# heatingHeaderEQ3.net
KiCad netlist of a schematic drawn in EAGLE
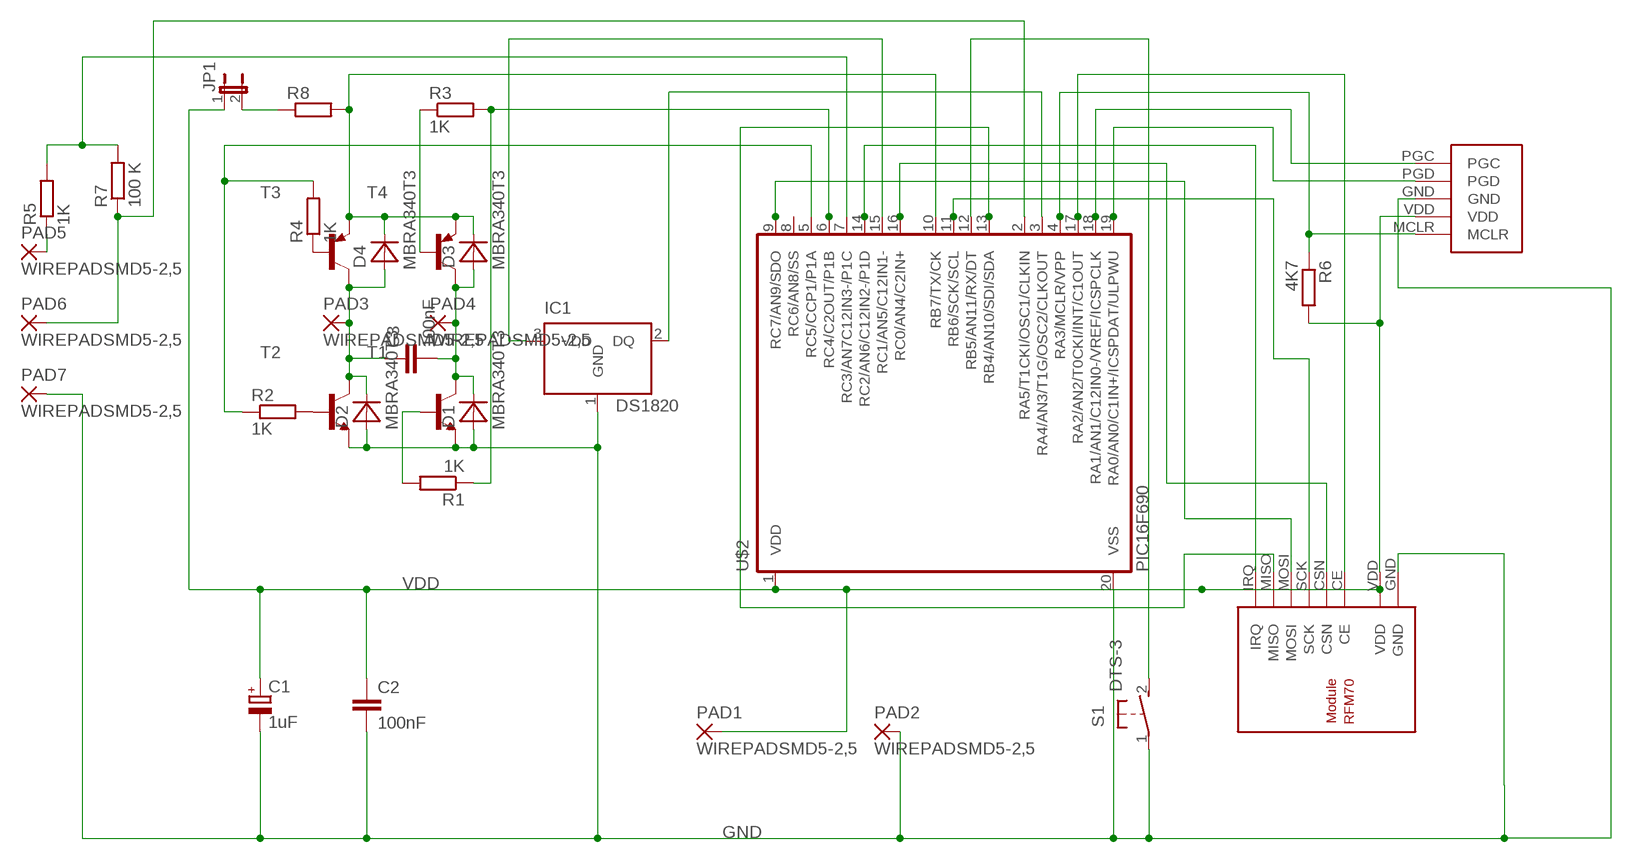
[diagram p0: schematic, sheet 1]

(export (version "E")
  (design (tool "Eeschema 10.0.6"))
  (components
    (comp (ref "C1")
      (value "1uF")
      (footprint "eagle-import:SMC_A")
      (libsource (lib "eagle-import") (part "CPOL-EUSMCA"))
    )
    (comp (ref "C2")
      (value "100nF")
      (footprint "eagle-import:C2012")
      (libsource (lib "eagle-import") (part "C-EUC2012"))
    )
    (comp (ref "C3")
      (value "100nF")
      (footprint "eagle-import:C2012")
      (libsource (lib "eagle-import") (part "C-EUC2012"))
    )
    (comp (ref "D1")
      (value "MBRA340T3")
      (footprint "eagle-import:SMA")
      (libsource (lib "eagle-import") (part "MBRA340T3"))
    )
    (comp (ref "D2")
      (value "MBRA340T3")
      (footprint "eagle-import:SMA")
      (libsource (lib "eagle-import") (part "MBRA340T3"))
    )
    (comp (ref "D3")
      (value "MBRA340T3")
      (footprint "eagle-import:SMA")
      (libsource (lib "eagle-import") (part "MBRA340T3"))
    )
    (comp (ref "D4")
      (value "MBRA340T3")
      (footprint "eagle-import:SMA")
      (libsource (lib "eagle-import") (part "MBRA340T3"))
    )
    (comp (ref "IC1")
      (value "DS1820")
      (footprint "eagle-import:TO-92")
      (libsource (lib "eagle-import") (part "DS1820"))
    )
    (comp (ref "JP1")
      (value "JP1E")
      (footprint "eagle-import:JP1")
      (libsource (lib "eagle-import") (part "JP1E"))
    )
    (comp (ref "PAD1")
      (value "WIREPADSMD5-2,5")
      (footprint "eagle-import:5-2,5")
      (libsource (lib "eagle-import") (part "WIREPADSMD5-2,5"))
    )
    (comp (ref "PAD2")
      (value "WIREPADSMD5-2,5")
      (footprint "eagle-import:5-2,5")
      (libsource (lib "eagle-import") (part "WIREPADSMD5-2,5"))
    )
    (comp (ref "PAD3")
      (value "WIREPADSMD5-2,5")
      (footprint "eagle-import:5-2,5")
      (libsource (lib "eagle-import") (part "WIREPADSMD5-2,5"))
    )
    (comp (ref "PAD4")
      (value "WIREPADSMD5-2,5")
      (footprint "eagle-import:5-2,5")
      (libsource (lib "eagle-import") (part "WIREPADSMD5-2,5"))
    )
    (comp (ref "PAD5")
      (value "WIREPADSMD5-2,5")
      (footprint "eagle-import:5-2,5")
      (libsource (lib "eagle-import") (part "WIREPADSMD5-2,5"))
    )
    (comp (ref "PAD6")
      (value "WIREPADSMD5-2,5")
      (footprint "eagle-import:5-2,5")
      (libsource (lib "eagle-import") (part "WIREPADSMD5-2,5"))
    )
    (comp (ref "PAD7")
      (value "WIREPADSMD5-2,5")
      (footprint "eagle-import:5-2,5")
      (libsource (lib "eagle-import") (part "WIREPADSMD5-2,5"))
    )
    (comp (ref "R1")
      (value "1K")
      (footprint "eagle-import:R1206")
      (libsource (lib "eagle-import") (part "R-EU_R1206"))
    )
    (comp (ref "R2")
      (value "1K")
      (footprint "eagle-import:R1206")
      (libsource (lib "eagle-import") (part "R-EU_R1206"))
    )
    (comp (ref "R3")
      (value "1K")
      (footprint "eagle-import:R1206")
      (libsource (lib "eagle-import") (part "R-EU_R1206"))
    )
    (comp (ref "R4")
      (value "1K")
      (footprint "eagle-import:R1206")
      (libsource (lib "eagle-import") (part "R-EU_R1206"))
    )
    (comp (ref "R5")
      (value "1K")
      (footprint "eagle-import:R1206")
      (libsource (lib "eagle-import") (part "R-EU_R1206"))
    )
    (comp (ref "R6")
      (value "4K7")
      (footprint "eagle-import:R1206W")
      (libsource (lib "eagle-import") (part "R-EU_R1206W"))
    )
    (comp (ref "R7")
      (value "100 K")
      (footprint "eagle-import:R1206")
      (libsource (lib "eagle-import") (part "R-EU_R1206"))
    )
    (comp (ref "R8")
      (value "R-EU_R2512W")
      (footprint "eagle-import:R2512W")
      (libsource (lib "eagle-import") (part "R-EU_R2512W"))
    )
    (comp (ref "S1")
      (value "DTS-3")
      (footprint "eagle-import:DTS-3")
      (libsource (lib "eagle-import") (part "DTS-3"))
    )
    (comp (ref "T1")
      (value "BC817-40-NPN-SOT23-BEC")
      (footprint "eagle-import:SOT23-BEC")
      (libsource (lib "eagle-import") (part "-NPN-SOT23-BECBC817-40"))
    )
    (comp (ref "T2")
      (value "BC817-40-NPN-SOT23-BEC")
      (footprint "eagle-import:SOT23-BEC")
      (libsource (lib "eagle-import") (part "-NPN-SOT23-BECBC817-40"))
    )
    (comp (ref "T3")
      (value "BC807-16-PNP-SOT23-BEC")
      (footprint "eagle-import:SOT23-BEC")
      (libsource (lib "eagle-import") (part "-PNP-SOT23-BECBC807-16"))
    )
    (comp (ref "T4")
      (value "BC807-16-PNP-SOT23-BEC")
      (footprint "eagle-import:SOT23-BEC")
      (libsource (lib "eagle-import") (part "-PNP-SOT23-BECBC807-16"))
    )
    (comp (ref "U$1")
      (value "RFM70")
      (footprint "eagle-import:RFM70")
      (libsource (lib "eagle-import") (part "RFM70"))
    )
    (comp (ref "U$2")
      (value "PIC16F690")
      (footprint "eagle-import:SSOP20")
      (libsource (lib "eagle-import") (part "PIC16F690"))
    )
    (comp (ref "U$3")
      (value "PROGRAMMINGHEADERDIP")
      (footprint "eagle-import:PROGHEADER")
      (libsource (lib "eagle-import") (part "PROGRAMMINGHEADERDIP"))
    )
  )
  (nets
    (net (code "1") (name "/GND") (class "Default")
      (node (ref "C1") (pin "-") (pinfunction "-_-") (pintype "passive"))
      (node (ref "C2") (pin "2") (pinfunction "2_2") (pintype "passive"))
      (node (ref "D1") (pin "A") (pinfunction "A_A") (pintype "passive"))
      (node (ref "D2") (pin "A") (pinfunction "A_A") (pintype "passive"))
      (node (ref "IC1") (pin "1") (pinfunction "GND_1") (pintype "power_in"))
      (node (ref "PAD2") (pin "1") (pinfunction "P_1") (pintype "passive"))
      (node (ref "PAD7") (pin "1") (pinfunction "P_1") (pintype "passive"))
      (node (ref "S1") (pin "1") (pinfunction "1_1") (pintype "passive"))
      (node (ref "T1") (pin "E") (pinfunction "E_E") (pintype "passive"))
      (node (ref "T2") (pin "E") (pinfunction "E_E") (pintype "passive"))
      (node (ref "U$1") (pin "GND") (pinfunction "GND_GND") (pintype "power_in"))
      (node (ref "U$2") (pin "20") (pinfunction "VSS_20") (pintype "power_in"))
      (node (ref "U$3") (pin "GND") (pinfunction "GND_GND") (pintype "power_in"))
    )
    (net (code "2") (name "/VDD") (class "Default")
      (node (ref "C1") (pin "+") (pinfunction "+_+") (pintype "passive"))
      (node (ref "C2") (pin "1") (pinfunction "1_1") (pintype "passive"))
      (node (ref "JP1") (pin "1") (pinfunction "1_1") (pintype "passive"))
      (node (ref "PAD1") (pin "1") (pinfunction "P_1") (pintype "passive"))
      (node (ref "R6") (pin "2") (pinfunction "2_2") (pintype "passive"))
      (node (ref "U$1") (pin "VDD") (pinfunction "VDD_VDD") (pintype "power_in"))
      (node (ref "U$2") (pin "1") (pinfunction "VDD_1") (pintype "power_in"))
      (node (ref "U$3") (pin "VDD") (pinfunction "VDD_VDD") (pintype "power_in"))
    )
    (net (code "3") (name "Net-(IC1-DQ)") (class "Default")
      (node (ref "IC1") (pin "2") (pinfunction "DQ_2") (pintype "output"))
      (node (ref "U$2") (pin "3") (pinfunction "RA4/AN3/T1G/OSC2/CLKOUT_3") (pintype "bidirectional"))
    )
    (net (code "4") (name "Net-(IC1-VDD)") (class "Default")
      (node (ref "IC1") (pin "3") (pinfunction "VDD_3") (pintype "input"))
      (node (ref "U$2") (pin "15") (pinfunction "RC1/AN5/C12IN1-_15") (pintype "bidirectional"))
    )
    (net (code "5") (name "Net-(JP1-Pad2)") (class "Default")
      (node (ref "JP1") (pin "2") (pinfunction "2_2") (pintype "passive"))
      (node (ref "R8") (pin "1") (pinfunction "1_1") (pintype "passive"))
    )
    (net (code "6") (name "Net-(PAD3-P)") (class "Default")
      (node (ref "C3") (pin "1") (pinfunction "1_1") (pintype "passive"))
      (node (ref "D2") (pin "C") (pinfunction "C_C") (pintype "passive"))
      (node (ref "D4") (pin "A") (pinfunction "A_A") (pintype "passive"))
      (node (ref "PAD3") (pin "1") (pinfunction "P_1") (pintype "passive"))
      (node (ref "T2") (pin "C") (pinfunction "C_C") (pintype "passive"))
      (node (ref "T3") (pin "C") (pinfunction "C_C") (pintype "passive"))
    )
    (net (code "7") (name "Net-(PAD4-P)") (class "Default")
      (node (ref "C3") (pin "2") (pinfunction "2_2") (pintype "passive"))
      (node (ref "D1") (pin "C") (pinfunction "C_C") (pintype "passive"))
      (node (ref "D3") (pin "A") (pinfunction "A_A") (pintype "passive"))
      (node (ref "PAD4") (pin "1") (pinfunction "P_1") (pintype "passive"))
      (node (ref "T1") (pin "C") (pinfunction "C_C") (pintype "passive"))
      (node (ref "T4") (pin "C") (pinfunction "C_C") (pintype "passive"))
    )
    (net (code "8") (name "Net-(PAD5-P)") (class "Default")
      (node (ref "PAD5") (pin "1") (pinfunction "P_1") (pintype "passive"))
      (node (ref "R5") (pin "1") (pinfunction "1_1") (pintype "passive"))
    )
    (net (code "9") (name "Net-(PAD6-P)") (class "Default")
      (node (ref "PAD6") (pin "1") (pinfunction "P_1") (pintype "passive"))
      (node (ref "R7") (pin "1") (pinfunction "1_1") (pintype "passive"))
      (node (ref "U$2") (pin "2") (pinfunction "RA5/T1CKI/OSC1/CLKIN_2") (pintype "bidirectional"))
    )
    (net (code "10") (name "Net-(R1-Pad2)") (class "Default")
      (node (ref "R1") (pin "2") (pinfunction "2_2") (pintype "passive"))
      (node (ref "T1") (pin "B") (pinfunction "B_B") (pintype "passive"))
    )
    (net (code "11") (name "Net-(R2-Pad2)") (class "Default")
      (node (ref "R2") (pin "2") (pinfunction "2_2") (pintype "passive"))
      (node (ref "T2") (pin "B") (pinfunction "B_B") (pintype "passive"))
    )
    (net (code "12") (name "Net-(R3-Pad1)") (class "Default")
      (node (ref "R3") (pin "1") (pinfunction "1_1") (pintype "passive"))
      (node (ref "T4") (pin "B") (pinfunction "B_B") (pintype "passive"))
    )
    (net (code "13") (name "Net-(R4-Pad1)") (class "Default")
      (node (ref "R4") (pin "1") (pinfunction "1_1") (pintype "passive"))
      (node (ref "T3") (pin "B") (pinfunction "B_B") (pintype "passive"))
    )
    (net (code "14") (name "Net-(U$2-RA0{slash}AN0{slash}C1IN+{slash}ICSPDAT{slash}ULPWU)") (class "Default")
      (node (ref "U$2") (pin "19") (pinfunction "RA0/AN0/C1IN+/ICSPDAT/ULPWU_19") (pintype "bidirectional"))
      (node (ref "U$3") (pin "PGD") (pinfunction "PGD_PGD") (pintype "bidirectional"))
    )
    (net (code "15") (name "Net-(U$2-RA1{slash}AN1{slash}C12IN0-{slash}VREF{slash}ICSPCLK)") (class "Default")
      (node (ref "U$2") (pin "18") (pinfunction "RA1/AN1/C12IN0-/VREF/ICSPCLK_18") (pintype "bidirectional"))
      (node (ref "U$3") (pin "PGC") (pinfunction "PGC_PGC") (pintype "bidirectional"))
    )
    (net (code "16") (name "Net-(U$2-RA2{slash}AN2{slash}T0CKI{slash}INT{slash}C1OUT)") (class "Default")
      (node (ref "U$1") (pin "CE") (pinfunction "CE_CE") (pintype "bidirectional"))
      (node (ref "U$2") (pin "17") (pinfunction "RA2/AN2/T0CKI/INT/C1OUT_17") (pintype "bidirectional"))
    )
    (net (code "17") (name "Net-(U$2-RA3{slash}MCLR{slash}VPP)") (class "Default")
      (node (ref "R6") (pin "1") (pinfunction "1_1") (pintype "passive"))
      (node (ref "U$2") (pin "4") (pinfunction "RA3/MCLR/VPP_4") (pintype "bidirectional"))
      (node (ref "U$3") (pin "MCLR") (pinfunction "MCLR_MCLR") (pintype "output"))
    )
    (net (code "18") (name "Net-(U$2-RB4{slash}AN10{slash}SDI{slash}SDA)") (class "Default")
      (node (ref "U$1") (pin "MISO") (pinfunction "MISO_MISO") (pintype "bidirectional"))
      (node (ref "U$2") (pin "13") (pinfunction "RB4/AN10/SDI/SDA_13") (pintype "bidirectional"))
    )
    (net (code "19") (name "Net-(U$2-RB5{slash}AN11{slash}RX{slash}DT)") (class "Default")
      (node (ref "S1") (pin "2") (pinfunction "2_2") (pintype "passive"))
      (node (ref "U$2") (pin "12") (pinfunction "RB5/AN11/RX/DT_12") (pintype "bidirectional"))
    )
    (net (code "20") (name "Net-(U$2-RB6{slash}SCK{slash}SCL)") (class "Default")
      (node (ref "U$1") (pin "SCK") (pinfunction "SCK_SCK") (pintype "bidirectional"))
      (node (ref "U$2") (pin "11") (pinfunction "RB6/SCK/SCL_11") (pintype "bidirectional"))
    )
    (net (code "21") (name "Net-(U$2-RB7{slash}TX{slash}CK)") (class "Default")
      (node (ref "D3") (pin "C") (pinfunction "C_C") (pintype "passive"))
      (node (ref "D4") (pin "C") (pinfunction "C_C") (pintype "passive"))
      (node (ref "R8") (pin "2") (pinfunction "2_2") (pintype "passive"))
      (node (ref "T3") (pin "E") (pinfunction "E_E") (pintype "passive"))
      (node (ref "T4") (pin "E") (pinfunction "E_E") (pintype "passive"))
      (node (ref "U$2") (pin "10") (pinfunction "RB7/TX/CK_10") (pintype "bidirectional"))
    )
    (net (code "22") (name "Net-(U$2-RC0{slash}AN4{slash}C2IN+)") (class "Default")
      (node (ref "U$1") (pin "CSN") (pinfunction "CSN_CSN") (pintype "bidirectional"))
      (node (ref "U$2") (pin "16") (pinfunction "RC0/AN4/C2IN+_16") (pintype "bidirectional"))
    )
    (net (code "23") (name "Net-(U$2-RC2{slash}AN6{slash}C12IN2-{slash}P1D)") (class "Default")
      (node (ref "U$1") (pin "IRQ") (pinfunction "IRQ_IRQ") (pintype "bidirectional"))
      (node (ref "U$2") (pin "14") (pinfunction "RC2/AN6/C12IN2-/P1D_14") (pintype "bidirectional"))
    )
    (net (code "24") (name "Net-(U$2-RC3{slash}AN7C12IN3-{slash}P1C)") (class "Default")
      (node (ref "R5") (pin "2") (pinfunction "2_2") (pintype "passive"))
      (node (ref "R7") (pin "2") (pinfunction "2_2") (pintype "passive"))
      (node (ref "U$2") (pin "7") (pinfunction "RC3/AN7C12IN3-/P1C_7") (pintype "bidirectional"))
    )
    (net (code "25") (name "Net-(U$2-RC4{slash}C2OUT{slash}P1B)") (class "Default")
      (node (ref "R1") (pin "1") (pinfunction "1_1") (pintype "passive"))
      (node (ref "R3") (pin "2") (pinfunction "2_2") (pintype "passive"))
      (node (ref "U$2") (pin "6") (pinfunction "RC4/C2OUT/P1B_6") (pintype "bidirectional"))
    )
    (net (code "26") (name "Net-(U$2-RC5{slash}CCP1{slash}P1A)") (class "Default")
      (node (ref "R2") (pin "1") (pinfunction "1_1") (pintype "passive"))
      (node (ref "R4") (pin "2") (pinfunction "2_2") (pintype "passive"))
      (node (ref "U$2") (pin "5") (pinfunction "RC5/CCP1/P1A_5") (pintype "bidirectional"))
    )
    (net (code "27") (name "Net-(U$2-RC7{slash}AN9{slash}SDO)") (class "Default")
      (node (ref "U$1") (pin "MOSI") (pinfunction "MOSI_MOSI") (pintype "bidirectional"))
      (node (ref "U$2") (pin "9") (pinfunction "RC7/AN9/SDO_9") (pintype "bidirectional"))
    )
    (net (code "28") (name "unconnected-(U$2-RC6{slash}AN8{slash}SS-Pad8)") (class "Default")
      (node (ref "U$2") (pin "8") (pinfunction "RC6/AN8/SS_8") (pintype "bidirectional"))
    )
  )
)
